# FPGA_NonIO.net
KiCad netlist of a schematic drawn in Altium Designer
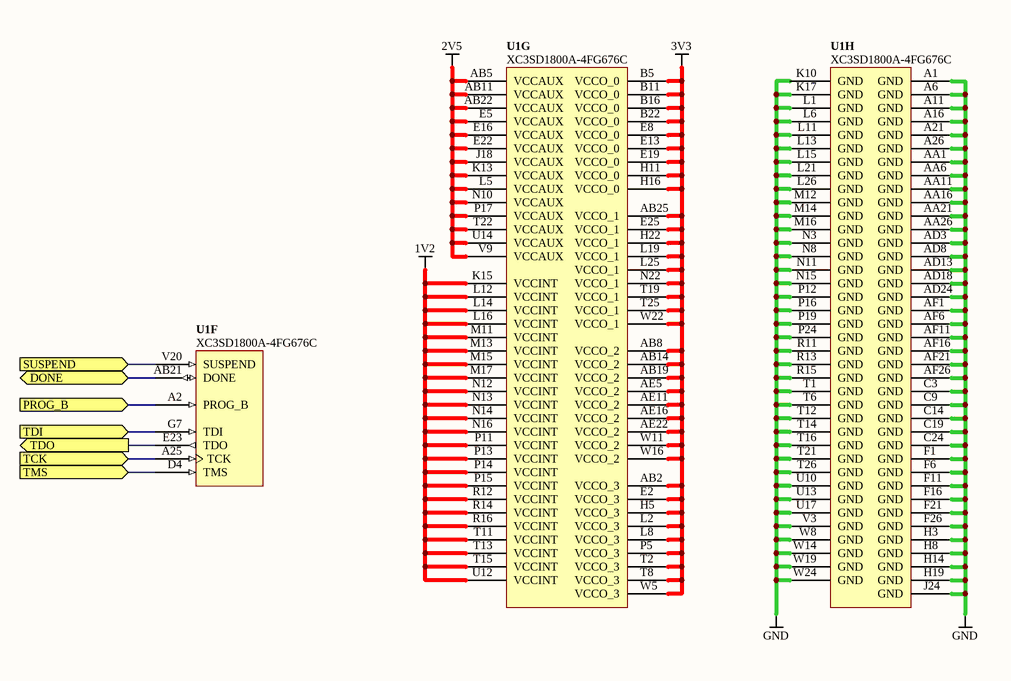
[diagram p0: FPGA_NonIO.SchDoc]

(export (version "E")
  (design (tool "Eeschema 10.0.6"))
  (components
    (comp (ref "U1")
      (value "XC3SD1800A-4FG676C")
      (footprint "BGA100P26X26-676")
      (description "FPGA, Xilinx Spartan 3A-DSP-1800 FG676")
      (libsource (lib "AltiumDesignLibrary") (part "XC3SD1800A-4FG676C"))
    )
  )
  (nets
    (net (code "1") (name "/DONE") (class "Default")
      (node (ref "U1") (pin "AB21") (pinfunction "DONE_AB21") (pintype "bidirectional"))
    )
    (net (code "2") (name "/PROG_B") (class "Default")
      (node (ref "U1") (pin "A2") (pinfunction "PROG_B_A2") (pintype "input"))
    )
    (net (code "3") (name "/SUSPEND") (class "Default")
      (node (ref "U1") (pin "V20") (pinfunction "SUSPEND_V20") (pintype "input"))
    )
    (net (code "4") (name "/TCK") (class "Default")
      (node (ref "U1") (pin "A25") (pinfunction "TCK_A25") (pintype "input"))
    )
    (net (code "5") (name "/TDI") (class "Default")
      (node (ref "U1") (pin "G7") (pinfunction "TDI_G7") (pintype "input"))
    )
    (net (code "6") (name "/TDO") (class "Default")
      (node (ref "U1") (pin "E23") (pinfunction "TDO_E23") (pintype "output"))
    )
    (net (code "7") (name "/TMS") (class "Default")
      (node (ref "U1") (pin "D4") (pinfunction "TMS_D4") (pintype "input"))
    )
    (net (code "8") (name "1V2") (class "Default")
      (node (ref "U1") (pin "K15") (pinfunction "VCCINT_K15") (pintype "power_in"))
      (node (ref "U1") (pin "L12") (pinfunction "VCCINT_L12") (pintype "power_in"))
      (node (ref "U1") (pin "L14") (pinfunction "VCCINT_L14") (pintype "power_in"))
      (node (ref "U1") (pin "L16") (pinfunction "VCCINT_L16") (pintype "power_in"))
      (node (ref "U1") (pin "M11") (pinfunction "VCCINT_M11") (pintype "power_in"))
      (node (ref "U1") (pin "M13") (pinfunction "VCCINT_M13") (pintype "power_in"))
      (node (ref "U1") (pin "M15") (pinfunction "VCCINT_M15") (pintype "power_in"))
      (node (ref "U1") (pin "M17") (pinfunction "VCCINT_M17") (pintype "power_in"))
      (node (ref "U1") (pin "N12") (pinfunction "VCCINT_N12") (pintype "power_in"))
      (node (ref "U1") (pin "N13") (pinfunction "VCCINT_N13") (pintype "power_in"))
      (node (ref "U1") (pin "N14") (pinfunction "VCCINT_N14") (pintype "power_in"))
      (node (ref "U1") (pin "N16") (pinfunction "VCCINT_N16") (pintype "power_in"))
      (node (ref "U1") (pin "P11") (pinfunction "VCCINT_P11") (pintype "power_in"))
      (node (ref "U1") (pin "P13") (pinfunction "VCCINT_P13") (pintype "power_in"))
      (node (ref "U1") (pin "P14") (pinfunction "VCCINT_P14") (pintype "power_in"))
      (node (ref "U1") (pin "P15") (pinfunction "VCCINT_P15") (pintype "power_in"))
      (node (ref "U1") (pin "R12") (pinfunction "VCCINT_R12") (pintype "power_in"))
      (node (ref "U1") (pin "R14") (pinfunction "VCCINT_R14") (pintype "power_in"))
      (node (ref "U1") (pin "R16") (pinfunction "VCCINT_R16") (pintype "power_in"))
      (node (ref "U1") (pin "T11") (pinfunction "VCCINT_T11") (pintype "power_in"))
      (node (ref "U1") (pin "T13") (pinfunction "VCCINT_T13") (pintype "power_in"))
      (node (ref "U1") (pin "T15") (pinfunction "VCCINT_T15") (pintype "power_in"))
      (node (ref "U1") (pin "U12") (pinfunction "VCCINT_U12") (pintype "power_in"))
    )
    (net (code "9") (name "2V5") (class "Default")
      (node (ref "U1") (pin "AB11") (pinfunction "VCCAUX_AB11") (pintype "power_in"))
      (node (ref "U1") (pin "AB22") (pinfunction "VCCAUX_AB22") (pintype "power_in"))
      (node (ref "U1") (pin "AB5") (pinfunction "VCCAUX_AB5") (pintype "power_in"))
      (node (ref "U1") (pin "E16") (pinfunction "VCCAUX_E16") (pintype "power_in"))
      (node (ref "U1") (pin "E22") (pinfunction "VCCAUX_E22") (pintype "power_in"))
      (node (ref "U1") (pin "E5") (pinfunction "VCCAUX_E5") (pintype "power_in"))
      (node (ref "U1") (pin "J18") (pinfunction "VCCAUX_J18") (pintype "power_in"))
      (node (ref "U1") (pin "K13") (pinfunction "VCCAUX_K13") (pintype "power_in"))
      (node (ref "U1") (pin "L5") (pinfunction "VCCAUX_L5") (pintype "power_in"))
      (node (ref "U1") (pin "N10") (pinfunction "VCCAUX_N10") (pintype "power_in"))
      (node (ref "U1") (pin "P17") (pinfunction "VCCAUX_P17") (pintype "power_in"))
      (node (ref "U1") (pin "T22") (pinfunction "VCCAUX_T22") (pintype "power_in"))
      (node (ref "U1") (pin "U14") (pinfunction "VCCAUX_U14") (pintype "power_in"))
      (node (ref "U1") (pin "V9") (pinfunction "VCCAUX_V9") (pintype "power_in"))
    )
    (net (code "10") (name "3V3") (class "Default")
      (node (ref "U1") (pin "AB14") (pinfunction "VCCO_2_AB14") (pintype "power_in"))
      (node (ref "U1") (pin "AB19") (pinfunction "VCCO_2_AB19") (pintype "power_in"))
      (node (ref "U1") (pin "AB2") (pinfunction "VCCO_3_AB2") (pintype "power_in"))
      (node (ref "U1") (pin "AB25") (pinfunction "VCCO_1_AB25") (pintype "power_in"))
      (node (ref "U1") (pin "AB8") (pinfunction "VCCO_2_AB8") (pintype "power_in"))
      (node (ref "U1") (pin "AE11") (pinfunction "VCCO_2_AE11") (pintype "power_in"))
      (node (ref "U1") (pin "AE16") (pinfunction "VCCO_2_AE16") (pintype "power_in"))
      (node (ref "U1") (pin "AE22") (pinfunction "VCCO_2_AE22") (pintype "power_in"))
      (node (ref "U1") (pin "AE5") (pinfunction "VCCO_2_AE5") (pintype "power_in"))
      (node (ref "U1") (pin "B11") (pinfunction "VCCO_0_B11") (pintype "power_in"))
      (node (ref "U1") (pin "B16") (pinfunction "VCCO_0_B16") (pintype "power_in"))
      (node (ref "U1") (pin "B22") (pinfunction "VCCO_0_B22") (pintype "power_in"))
      (node (ref "U1") (pin "B5") (pinfunction "VCCO_0_B5") (pintype "power_in"))
      (node (ref "U1") (pin "E13") (pinfunction "VCCO_0_E13") (pintype "power_in"))
      (node (ref "U1") (pin "E19") (pinfunction "VCCO_0_E19") (pintype "power_in"))
      (node (ref "U1") (pin "E2") (pinfunction "VCCO_3_E2") (pintype "power_in"))
      (node (ref "U1") (pin "E25") (pinfunction "VCCO_1_E25") (pintype "power_in"))
      (node (ref "U1") (pin "E8") (pinfunction "VCCO_0_E8") (pintype "power_in"))
      (node (ref "U1") (pin "H11") (pinfunction "VCCO_0_H11") (pintype "power_in"))
      (node (ref "U1") (pin "H16") (pinfunction "VCCO_0_H16") (pintype "power_in"))
      (node (ref "U1") (pin "H22") (pinfunction "VCCO_1_H22") (pintype "power_in"))
      (node (ref "U1") (pin "H5") (pinfunction "VCCO_3_H5") (pintype "power_in"))
      (node (ref "U1") (pin "L19") (pinfunction "VCCO_1_L19") (pintype "power_in"))
      (node (ref "U1") (pin "L2") (pinfunction "VCCO_3_L2") (pintype "power_in"))
      (node (ref "U1") (pin "L25") (pinfunction "VCCO_1_L25") (pintype "power_in"))
      (node (ref "U1") (pin "L8") (pinfunction "VCCO_3_L8") (pintype "power_in"))
      (node (ref "U1") (pin "N22") (pinfunction "VCCO_1_N22") (pintype "power_in"))
      (node (ref "U1") (pin "P5") (pinfunction "VCCO_3_P5") (pintype "power_in"))
      (node (ref "U1") (pin "T19") (pinfunction "VCCO_1_T19") (pintype "power_in"))
      (node (ref "U1") (pin "T2") (pinfunction "VCCO_3_T2") (pintype "power_in"))
      (node (ref "U1") (pin "T25") (pinfunction "VCCO_1_T25") (pintype "power_in"))
      (node (ref "U1") (pin "T8") (pinfunction "VCCO_3_T8") (pintype "power_in"))
      (node (ref "U1") (pin "W11") (pinfunction "VCCO_2_W11") (pintype "power_in"))
      (node (ref "U1") (pin "W16") (pinfunction "VCCO_2_W16") (pintype "power_in"))
      (node (ref "U1") (pin "W22") (pinfunction "VCCO_1_W22") (pintype "power_in"))
      (node (ref "U1") (pin "W5") (pinfunction "VCCO_3_W5") (pintype "power_in"))
    )
    (net (code "11") (name "GND") (class "Default")
      (node (ref "U1") (pin "A1") (pinfunction "GND_A1") (pintype "power_in"))
      (node (ref "U1") (pin "A11") (pinfunction "GND_A11") (pintype "power_in"))
      (node (ref "U1") (pin "A16") (pinfunction "GND_A16") (pintype "power_in"))
      (node (ref "U1") (pin "A21") (pinfunction "GND_A21") (pintype "power_in"))
      (node (ref "U1") (pin "A26") (pinfunction "GND_A26") (pintype "power_in"))
      (node (ref "U1") (pin "A6") (pinfunction "GND_A6") (pintype "power_in"))
      (node (ref "U1") (pin "AA1") (pinfunction "GND_AA1") (pintype "power_in"))
      (node (ref "U1") (pin "AA11") (pinfunction "GND_AA11") (pintype "power_in"))
      (node (ref "U1") (pin "AA16") (pinfunction "GND_AA16") (pintype "power_in"))
      (node (ref "U1") (pin "AA21") (pinfunction "GND_AA21") (pintype "power_in"))
      (node (ref "U1") (pin "AA26") (pinfunction "GND_AA26") (pintype "power_in"))
      (node (ref "U1") (pin "AA6") (pinfunction "GND_AA6") (pintype "power_in"))
      (node (ref "U1") (pin "AD13") (pinfunction "GND_AD13") (pintype "power_in"))
      (node (ref "U1") (pin "AD18") (pinfunction "GND_AD18") (pintype "power_in"))
      (node (ref "U1") (pin "AD24") (pinfunction "GND_AD24") (pintype "power_in"))
      (node (ref "U1") (pin "AD3") (pinfunction "GND_AD3") (pintype "power_in"))
      (node (ref "U1") (pin "AD8") (pinfunction "GND_AD8") (pintype "power_in"))
      (node (ref "U1") (pin "AF1") (pinfunction "GND_AF1") (pintype "power_in"))
      (node (ref "U1") (pin "AF11") (pinfunction "GND_AF11") (pintype "power_in"))
      (node (ref "U1") (pin "AF16") (pinfunction "GND_AF16") (pintype "power_in"))
      (node (ref "U1") (pin "AF21") (pinfunction "GND_AF21") (pintype "power_in"))
      (node (ref "U1") (pin "AF26") (pinfunction "GND_AF26") (pintype "power_in"))
      (node (ref "U1") (pin "AF6") (pinfunction "GND_AF6") (pintype "power_in"))
      (node (ref "U1") (pin "C14") (pinfunction "GND_C14") (pintype "power_in"))
      (node (ref "U1") (pin "C19") (pinfunction "GND_C19") (pintype "power_in"))
      (node (ref "U1") (pin "C24") (pinfunction "GND_C24") (pintype "power_in"))
      (node (ref "U1") (pin "C3") (pinfunction "GND_C3") (pintype "power_in"))
      (node (ref "U1") (pin "C9") (pinfunction "GND_C9") (pintype "power_in"))
      (node (ref "U1") (pin "F1") (pinfunction "GND_F1") (pintype "power_in"))
      (node (ref "U1") (pin "F11") (pinfunction "GND_F11") (pintype "power_in"))
      (node (ref "U1") (pin "F16") (pinfunction "GND_F16") (pintype "power_in"))
      (node (ref "U1") (pin "F21") (pinfunction "GND_F21") (pintype "power_in"))
      (node (ref "U1") (pin "F26") (pinfunction "GND_F26") (pintype "power_in"))
      (node (ref "U1") (pin "F6") (pinfunction "GND_F6") (pintype "power_in"))
      (node (ref "U1") (pin "H14") (pinfunction "GND_H14") (pintype "power_in"))
      (node (ref "U1") (pin "H19") (pinfunction "GND_H19") (pintype "power_in"))
      (node (ref "U1") (pin "H3") (pinfunction "GND_H3") (pintype "power_in"))
      (node (ref "U1") (pin "H8") (pinfunction "GND_H8") (pintype "power_in"))
      (node (ref "U1") (pin "J24") (pinfunction "GND_J24") (pintype "power_in"))
      (node (ref "U1") (pin "K10") (pinfunction "GND_K10") (pintype "power_in"))
      (node (ref "U1") (pin "K17") (pinfunction "GND_K17") (pintype "power_in"))
      (node (ref "U1") (pin "L1") (pinfunction "GND_L1") (pintype "power_in"))
      (node (ref "U1") (pin "L11") (pinfunction "GND_L11") (pintype "power_in"))
      (node (ref "U1") (pin "L13") (pinfunction "GND_L13") (pintype "power_in"))
      (node (ref "U1") (pin "L15") (pinfunction "GND_L15") (pintype "power_in"))
      (node (ref "U1") (pin "L21") (pinfunction "GND_L21") (pintype "power_in"))
      (node (ref "U1") (pin "L26") (pinfunction "GND_L26") (pintype "power_in"))
      (node (ref "U1") (pin "L6") (pinfunction "GND_L6") (pintype "power_in"))
      (node (ref "U1") (pin "M12") (pinfunction "GND_M12") (pintype "power_in"))
      (node (ref "U1") (pin "M14") (pinfunction "GND_M14") (pintype "power_in"))
      (node (ref "U1") (pin "M16") (pinfunction "GND_M16") (pintype "power_in"))
      (node (ref "U1") (pin "N11") (pinfunction "GND_N11") (pintype "power_in"))
      (node (ref "U1") (pin "N15") (pinfunction "GND_N15") (pintype "power_in"))
      (node (ref "U1") (pin "N3") (pinfunction "GND_N3") (pintype "power_in"))
      (node (ref "U1") (pin "N8") (pinfunction "GND_N8") (pintype "power_in"))
      (node (ref "U1") (pin "P12") (pinfunction "GND_P12") (pintype "power_in"))
      (node (ref "U1") (pin "P16") (pinfunction "GND_P16") (pintype "power_in"))
      (node (ref "U1") (pin "P19") (pinfunction "GND_P19") (pintype "power_in"))
      (node (ref "U1") (pin "P24") (pinfunction "GND_P24") (pintype "power_in"))
      (node (ref "U1") (pin "R11") (pinfunction "GND_R11") (pintype "power_in"))
      (node (ref "U1") (pin "R13") (pinfunction "GND_R13") (pintype "power_in"))
      (node (ref "U1") (pin "R15") (pinfunction "GND_R15") (pintype "power_in"))
      (node (ref "U1") (pin "T1") (pinfunction "GND_T1") (pintype "power_in"))
      (node (ref "U1") (pin "T12") (pinfunction "GND_T12") (pintype "power_in"))
      (node (ref "U1") (pin "T14") (pinfunction "GND_T14") (pintype "power_in"))
      (node (ref "U1") (pin "T16") (pinfunction "GND_T16") (pintype "power_in"))
      (node (ref "U1") (pin "T21") (pinfunction "GND_T21") (pintype "power_in"))
      (node (ref "U1") (pin "T26") (pinfunction "GND_T26") (pintype "power_in"))
      (node (ref "U1") (pin "T6") (pinfunction "GND_T6") (pintype "power_in"))
      (node (ref "U1") (pin "U10") (pinfunction "GND_U10") (pintype "power_in"))
      (node (ref "U1") (pin "U13") (pinfunction "GND_U13") (pintype "power_in"))
      (node (ref "U1") (pin "U17") (pinfunction "GND_U17") (pintype "power_in"))
      (node (ref "U1") (pin "V3") (pinfunction "GND_V3") (pintype "power_in"))
      (node (ref "U1") (pin "W14") (pinfunction "GND_W14") (pintype "power_in"))
      (node (ref "U1") (pin "W19") (pinfunction "GND_W19") (pintype "power_in"))
      (node (ref "U1") (pin "W24") (pinfunction "GND_W24") (pintype "power_in"))
      (node (ref "U1") (pin "W8") (pinfunction "GND_W8") (pintype "power_in"))
    )
  )
)
